# SCH_SD-pcb-t14_2026-02-01.net
KiCad netlist of a schematic drawn in EasyEDA
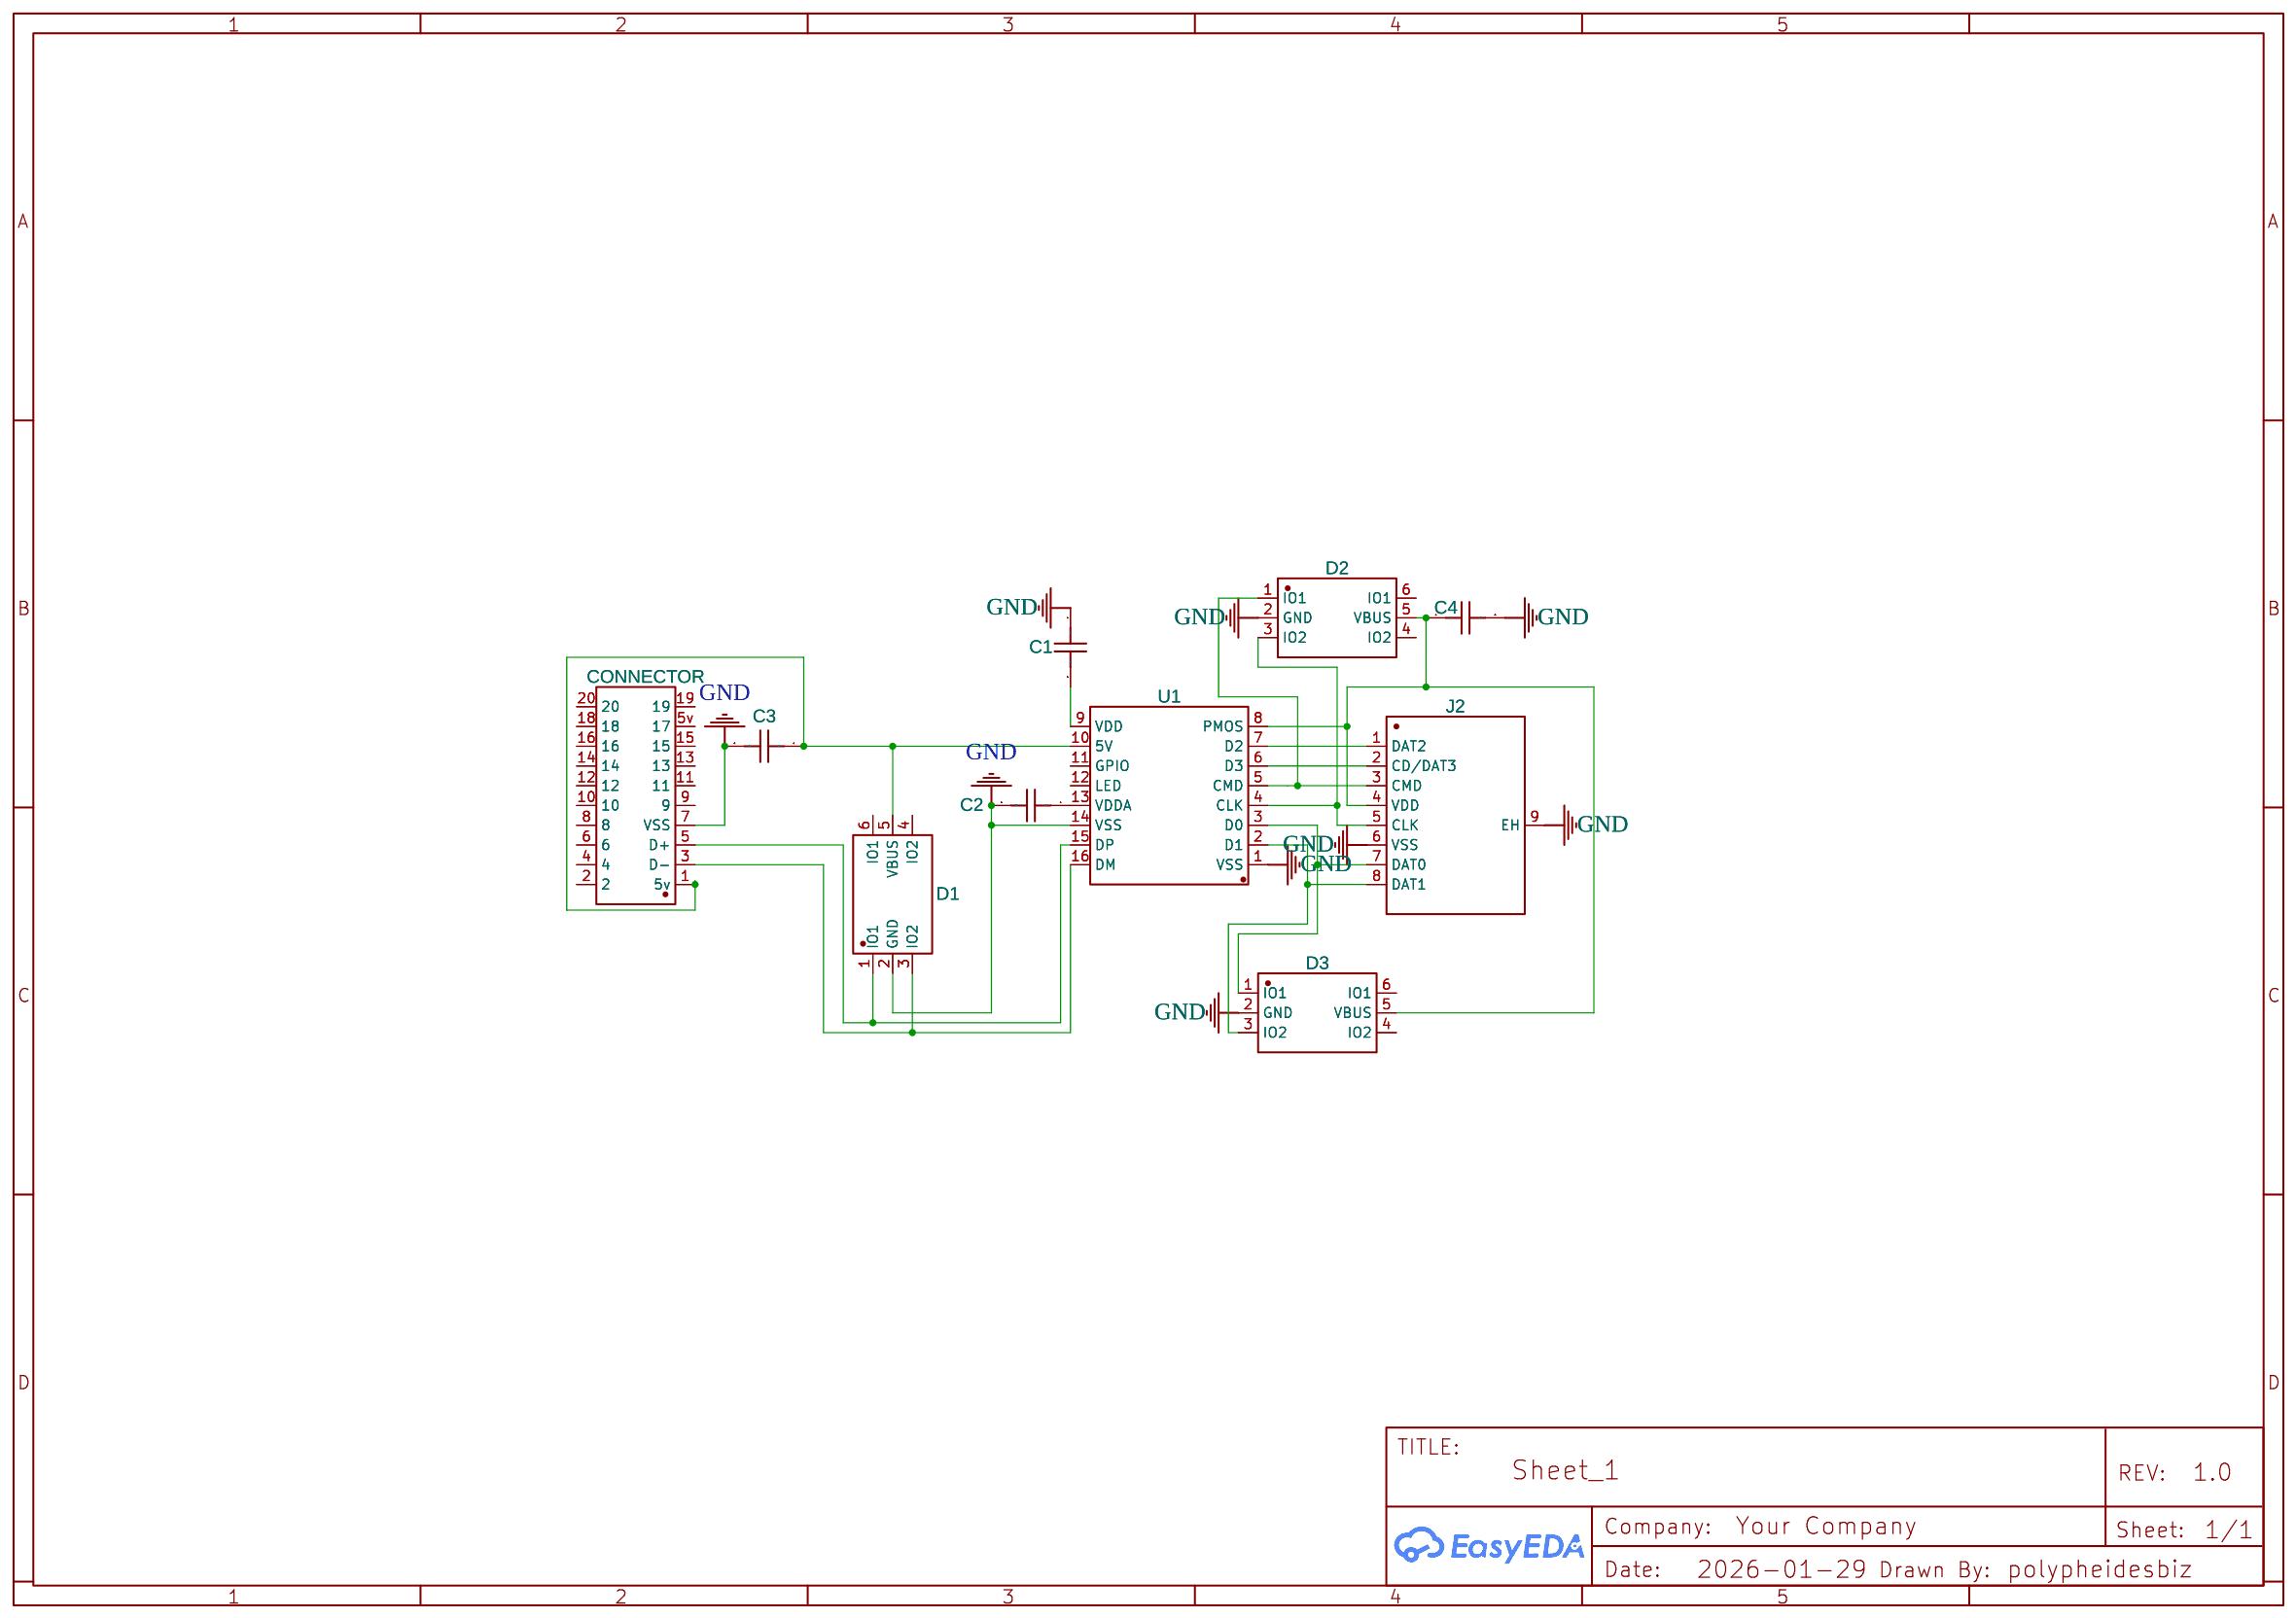
[diagram p0: schematic sheet]

(export (version "E")
  (design (tool "Eeschema 10.0.6"))
  (components
    (comp (ref "C1")
      (value "100nF")
      (fields
        (field (name "Manufacturer Part") "AC0603KRX7R8BB104")
        (field (name "Manufacturer") "YAGEO(国巨)")
      )
      (libsource (lib "") (part "AC0603KRX7R8BB104"))
    )
    (comp (ref "C2")
      (value "100nF")
      (fields
        (field (name "Manufacturer Part") "AC0603KRX7R8BB104")
        (field (name "Manufacturer") "YAGEO(国巨)")
      )
      (libsource (lib "") (part "AC0603KRX7R8BB104_1"))
    )
    (comp (ref "C3")
      (value "100nF")
      (fields
        (field (name "Manufacturer Part") "AC0603KRX7R8BB104")
        (field (name "Manufacturer") "YAGEO(国巨)")
      )
      (libsource (lib "") (part "AC0603KRX7R8BB104_1"))
    )
    (comp (ref "C4")
      (value "100nF")
      (fields
        (field (name "Manufacturer Part") "AC0603KRX7R8BB104")
        (field (name "Manufacturer") "YAGEO(国巨)")
      )
      (libsource (lib "") (part "AC0603KRX7R8BB104_2"))
    )
    (comp (ref "CONNECTOR")
      (value "DF40C-20DS-0.4V(51)")
      (fields (field (name "Manufacturer") "HRS(广濑)"))
      (libsource (lib "") (part "DF40C-20DS-0.4V(51)"))
    )
    (comp (ref "D1")
      (value "USBLC6-2SC6_C2827654")
      (fields
        (field (name "Manufacturer Part") "USBLC6-2SC6")
        (field (name "Manufacturer") "TECH PUBLIC(台舟)")
      )
      (libsource (lib "") (part "USBLC6-2SC6_C2827654_1"))
    )
    (comp (ref "D2")
      (value "USBLC6-2SC6_C2827654")
      (fields
        (field (name "Manufacturer Part") "USBLC6-2SC6")
        (field (name "Manufacturer") "TECH PUBLIC(台舟)")
      )
      (libsource (lib "") (part "USBLC6-2SC6_C2827654"))
    )
    (comp (ref "D3")
      (value "USBLC6-2SC6_C2827654")
      (fields
        (field (name "Manufacturer Part") "USBLC6-2SC6")
        (field (name "Manufacturer") "TECH PUBLIC(台舟)")
      )
      (libsource (lib "") (part "USBLC6-2SC6_C2827654"))
    )
    (comp (ref "J2")
      (value "TF-009")
      (fields (field (name "Manufacturer") "SOFNG(硕方)"))
      (libsource (lib "") (part "TF-009"))
    )
    (comp (ref "U1")
      (value "GL823K-HCY04")
      (fields (field (name "Manufacturer") "GENESYS(创惟)"))
      (libsource (lib "") (part "GL823K-HCY04"))
    )
  )
  (nets
    (net (code "1") (name "GND") (class "Default")
      (node (ref "C1") (pin "1") (pinfunction "1_1") (pintype "unspecified"))
      (node (ref "C2") (pin "2") (pinfunction "2_2") (pintype "unspecified"))
      (node (ref "C3") (pin "2") (pinfunction "2_2") (pintype "unspecified"))
      (node (ref "C4") (pin "2") (pinfunction "2_2") (pintype "unspecified"))
      (node (ref "CONNECTOR") (pin "7") (pinfunction "VSS_7") (pintype "unspecified"))
      (node (ref "D1") (pin "2") (pinfunction "GND_2") (pintype "unspecified"))
      (node (ref "D2") (pin "2") (pinfunction "GND_2") (pintype "unspecified"))
      (node (ref "D3") (pin "2") (pinfunction "GND_2") (pintype "unspecified"))
      (node (ref "J2") (pin "6") (pinfunction "VSS_6") (pintype "unspecified"))
      (node (ref "J2") (pin "9") (pinfunction "EH_9") (pintype "unspecified"))
      (node (ref "U1") (pin "1") (pinfunction "VSS_1") (pintype "unspecified"))
      (node (ref "U1") (pin "14") (pinfunction "VSS_14") (pintype "unspecified"))
    )
    (net (code "2") (name "Net-(CONNECTOR-5v)") (class "Default")
      (node (ref "C3") (pin "1") (pinfunction "1_1") (pintype "unspecified"))
      (node (ref "CONNECTOR") (pin "1") (pinfunction "5v_1") (pintype "unspecified"))
      (node (ref "D1") (pin "5") (pinfunction "VBUS_5") (pintype "unspecified"))
      (node (ref "U1") (pin "10") (pinfunction "5V_10") (pintype "unspecified"))
    )
    (net (code "3") (name "Net-(CONNECTOR-D+)") (class "Default")
      (node (ref "CONNECTOR") (pin "5") (pinfunction "D+_5") (pintype "unspecified"))
      (node (ref "D1") (pin "1") (pinfunction "IO1_1") (pintype "unspecified"))
      (node (ref "U1") (pin "15") (pinfunction "DP_15") (pintype "unspecified"))
    )
    (net (code "4") (name "Net-(CONNECTOR-D-)") (class "Default")
      (node (ref "CONNECTOR") (pin "3") (pinfunction "D-_3") (pintype "unspecified"))
      (node (ref "D1") (pin "3") (pinfunction "IO2_3") (pintype "unspecified"))
      (node (ref "U1") (pin "16") (pinfunction "DM_16") (pintype "unspecified"))
    )
    (net (code "5") (name "Net-(D2-VBUS)") (class "Default")
      (node (ref "C4") (pin "1") (pinfunction "1_1") (pintype "unspecified"))
      (node (ref "D2") (pin "5") (pinfunction "VBUS_5") (pintype "unspecified"))
      (node (ref "D3") (pin "5") (pinfunction "VBUS_5") (pintype "unspecified"))
      (node (ref "J2") (pin "4") (pinfunction "VDD_4") (pintype "unspecified"))
      (node (ref "U1") (pin "8") (pinfunction "PMOS_8") (pintype "unspecified"))
    )
    (net (code "6") (name "Net-(J2-CD{slash}DAT3)") (class "Default")
      (node (ref "J2") (pin "2") (pinfunction "CD/DAT3_2") (pintype "unspecified"))
      (node (ref "U1") (pin "6") (pinfunction "D3_6") (pintype "unspecified"))
    )
    (net (code "7") (name "Net-(J2-CLK)") (class "Default")
      (node (ref "D2") (pin "3") (pinfunction "IO2_3") (pintype "unspecified"))
      (node (ref "J2") (pin "5") (pinfunction "CLK_5") (pintype "unspecified"))
      (node (ref "U1") (pin "4") (pinfunction "CLK_4") (pintype "unspecified"))
    )
    (net (code "8") (name "Net-(J2-CMD)") (class "Default")
      (node (ref "D2") (pin "1") (pinfunction "IO1_1") (pintype "unspecified"))
      (node (ref "J2") (pin "3") (pinfunction "CMD_3") (pintype "unspecified"))
      (node (ref "U1") (pin "5") (pinfunction "CMD_5") (pintype "unspecified"))
    )
    (net (code "9") (name "Net-(J2-DAT0)") (class "Default")
      (node (ref "D3") (pin "1") (pinfunction "IO1_1") (pintype "unspecified"))
      (node (ref "J2") (pin "7") (pinfunction "DAT0_7") (pintype "unspecified"))
      (node (ref "U1") (pin "3") (pinfunction "D0_3") (pintype "unspecified"))
    )
    (net (code "10") (name "Net-(J2-DAT1)") (class "Default")
      (node (ref "D3") (pin "3") (pinfunction "IO2_3") (pintype "unspecified"))
      (node (ref "J2") (pin "8") (pinfunction "DAT1_8") (pintype "unspecified"))
      (node (ref "U1") (pin "2") (pinfunction "D1_2") (pintype "unspecified"))
    )
    (net (code "11") (name "Net-(J2-DAT2)") (class "Default")
      (node (ref "J2") (pin "1") (pinfunction "DAT2_1") (pintype "unspecified"))
      (node (ref "U1") (pin "7") (pinfunction "D2_7") (pintype "unspecified"))
    )
    (net (code "12") (name "Net-(U1-VDD)") (class "Default")
      (node (ref "C1") (pin "2") (pinfunction "2_2") (pintype "unspecified"))
      (node (ref "U1") (pin "9") (pinfunction "VDD_9") (pintype "unspecified"))
    )
    (net (code "13") (name "Net-(U1-VDDA)") (class "Default")
      (node (ref "C2") (pin "1") (pinfunction "1_1") (pintype "unspecified"))
      (node (ref "U1") (pin "13") (pinfunction "VDDA_13") (pintype "unspecified"))
    )
    (net (code "14") (name "unconnected-(CONNECTOR-17-Pad5v)") (class "Default")
      (node (ref "CONNECTOR") (pin "5v") (pinfunction "17_5v") (pintype "unspecified"))
    )
    (net (code "15") (name "unconnected-(CONNECTOR-Pad2)") (class "Default")
      (node (ref "CONNECTOR") (pin "2") (pinfunction "2_2") (pintype "unspecified"))
    )
    (net (code "16") (name "unconnected-(CONNECTOR-Pad4)") (class "Default")
      (node (ref "CONNECTOR") (pin "4") (pinfunction "4_4") (pintype "unspecified"))
    )
    (net (code "17") (name "unconnected-(CONNECTOR-Pad6)") (class "Default")
      (node (ref "CONNECTOR") (pin "6") (pinfunction "6_6") (pintype "unspecified"))
    )
    (net (code "18") (name "unconnected-(CONNECTOR-Pad8)") (class "Default")
      (node (ref "CONNECTOR") (pin "8") (pinfunction "8_8") (pintype "unspecified"))
    )
    (net (code "19") (name "unconnected-(CONNECTOR-Pad9)") (class "Default")
      (node (ref "CONNECTOR") (pin "9") (pinfunction "9_9") (pintype "unspecified"))
    )
    (net (code "20") (name "unconnected-(CONNECTOR-Pad10)") (class "Default")
      (node (ref "CONNECTOR") (pin "10") (pinfunction "10_10") (pintype "unspecified"))
    )
    (net (code "21") (name "unconnected-(CONNECTOR-Pad11)") (class "Default")
      (node (ref "CONNECTOR") (pin "11") (pinfunction "11_11") (pintype "unspecified"))
    )
    (net (code "22") (name "unconnected-(CONNECTOR-Pad12)") (class "Default")
      (node (ref "CONNECTOR") (pin "12") (pinfunction "12_12") (pintype "unspecified"))
    )
    (net (code "23") (name "unconnected-(CONNECTOR-Pad13)") (class "Default")
      (node (ref "CONNECTOR") (pin "13") (pinfunction "13_13") (pintype "unspecified"))
    )
    (net (code "24") (name "unconnected-(CONNECTOR-Pad14)") (class "Default")
      (node (ref "CONNECTOR") (pin "14") (pinfunction "14_14") (pintype "unspecified"))
    )
    (net (code "25") (name "unconnected-(CONNECTOR-Pad15)") (class "Default")
      (node (ref "CONNECTOR") (pin "15") (pinfunction "15_15") (pintype "unspecified"))
    )
    (net (code "26") (name "unconnected-(CONNECTOR-Pad16)") (class "Default")
      (node (ref "CONNECTOR") (pin "16") (pinfunction "16_16") (pintype "unspecified"))
    )
    (net (code "27") (name "unconnected-(CONNECTOR-Pad18)") (class "Default")
      (node (ref "CONNECTOR") (pin "18") (pinfunction "18_18") (pintype "unspecified"))
    )
    (net (code "28") (name "unconnected-(CONNECTOR-Pad19)") (class "Default")
      (node (ref "CONNECTOR") (pin "19") (pinfunction "19_19") (pintype "unspecified"))
    )
    (net (code "29") (name "unconnected-(CONNECTOR-Pad20)") (class "Default")
      (node (ref "CONNECTOR") (pin "20") (pinfunction "20_20") (pintype "unspecified"))
    )
    (net (code "30") (name "unconnected-(D1-IO1-Pad6)") (class "Default")
      (node (ref "D1") (pin "6") (pinfunction "IO1_6") (pintype "unspecified"))
    )
    (net (code "31") (name "unconnected-(D1-IO2-Pad4)") (class "Default")
      (node (ref "D1") (pin "4") (pinfunction "IO2_4") (pintype "unspecified"))
    )
    (net (code "32") (name "unconnected-(D2-IO1-Pad6)") (class "Default")
      (node (ref "D2") (pin "6") (pinfunction "IO1_6") (pintype "unspecified"))
    )
    (net (code "33") (name "unconnected-(D2-IO2-Pad4)") (class "Default")
      (node (ref "D2") (pin "4") (pinfunction "IO2_4") (pintype "unspecified"))
    )
    (net (code "34") (name "unconnected-(D3-IO1-Pad6)") (class "Default")
      (node (ref "D3") (pin "6") (pinfunction "IO1_6") (pintype "unspecified"))
    )
    (net (code "35") (name "unconnected-(D3-IO2-Pad4)") (class "Default")
      (node (ref "D3") (pin "4") (pinfunction "IO2_4") (pintype "unspecified"))
    )
    (net (code "36") (name "unconnected-(U1-GPIO-Pad11)") (class "Default")
      (node (ref "U1") (pin "11") (pinfunction "GPIO_11") (pintype "unspecified"))
    )
    (net (code "37") (name "unconnected-(U1-LED-Pad12)") (class "Default")
      (node (ref "U1") (pin "12") (pinfunction "LED_12") (pintype "unspecified"))
    )
  )
)
